# PDM-S02-V00-BatteryProtection.net
KiCad netlist of a schematic drawn in Altium Designer
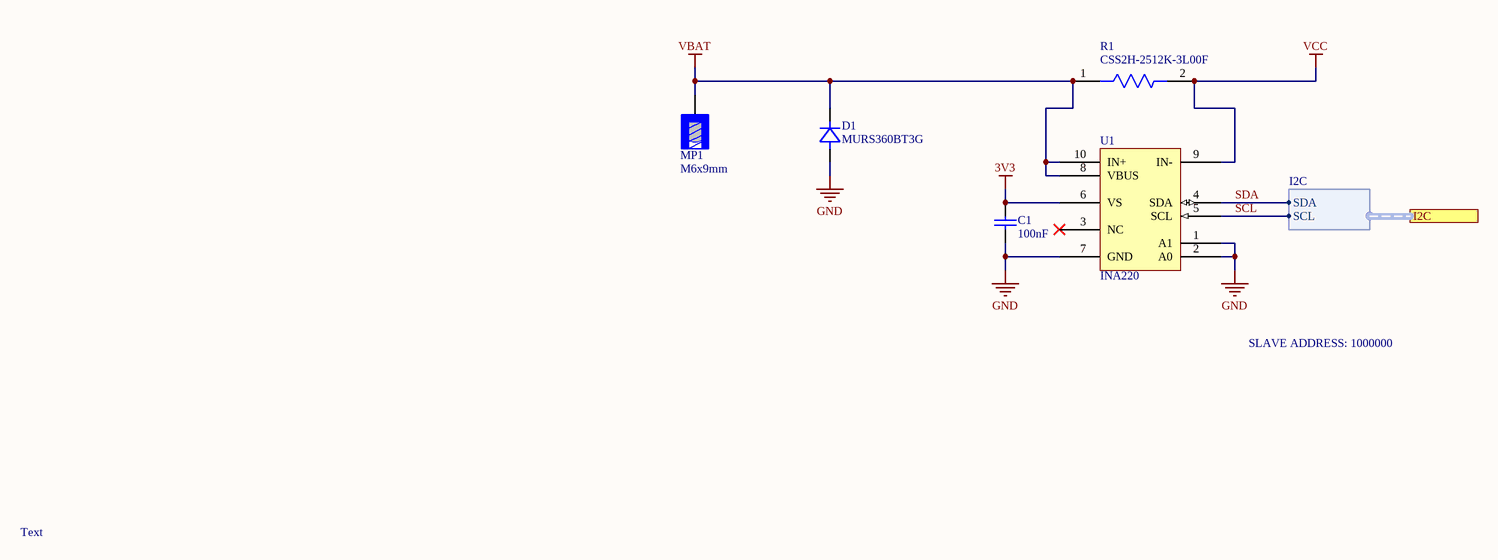
[diagram p0: PDM-S02-V00-BatteryProtection.SchDoc]

(export (version "E")
  (design (tool "Eeschema 10.0.6"))
  (components
    (comp (ref "C1")
      (value "100nF")
      (footprint "Cap_Ceramic_0603")
      (description "Capacitor, Ceramic, SMD, 100nF, 50V, 5%, X7R, 0603")
      (libsource (lib "StandardCapacitors") (part "100nF 50V 5% X7R 0603"))
    )
    (comp (ref "D1")
      (value "MURS360BT3G")
      (footprint "DO-214AA")
      (description "Diode Standard 600V 3A Surface Mount SMB")
      (libsource (lib "QUTMS_DiodeLibrary") (part "MURS360BT3G"))
    )
    (comp (ref "MP1")
      (value "M6x9mm")
      (footprint "7461084_for chemical surfaces")
      (description "WP-BUTR Press-Fit with Internal thread, two rows, 10x10mm, 8 pins, M6x9mm, 160A")
      (fields (field (name "PART NUMBER") "7461084") (field (name "PUBLISHER") "Wurth Elektronik"))
      (libsource (lib "7461084_Altium_WP-BUTR_rev19a") (part "7461084"))
    )
    (comp (ref "R1")
      (value "CSS2H-2512K-3L00F")
      (footprint "CSS2H-2512")
      (description "RES 0.003 OHM 1% 4W 2512")
      (libsource (lib "PDM-CARD-SCHLib-V00") (part "CSS2H-2512K-3L00F"))
    )
    (comp (ref "U1")
      (value "INA220")
      (footprint "VSSOP-10P")
      (libsource (lib "PDM-CARD-SCHLib-V00") (part "INA220"))
    )
  )
  (nets
    (net (code "2") (name "/SCL") (class "Default")
      (node (ref "U1") (pin "5") (pinfunction "SCL_5") (pintype "input"))
    )
    (net (code "3") (name "/SDA") (class "Default")
      (node (ref "U1") (pin "4") (pinfunction "SDA_4") (pintype "bidirectional"))
    )
    (net (code "5") (name "3V3") (class "Default")
      (node (ref "C1") (pin "2") (pinfunction "2_2") (pintype "passive"))
      (node (ref "U1") (pin "6") (pinfunction "VS_6") (pintype "passive"))
    )
    (net (code "6") (name "GND") (class "Default")
      (node (ref "C1") (pin "1") (pinfunction "1_1") (pintype "passive"))
      (node (ref "D1") (pin "A") (pinfunction "A_A") (pintype "passive"))
      (node (ref "U1") (pin "1") (pinfunction "A1_1") (pintype "passive"))
      (node (ref "U1") (pin "2") (pinfunction "A0_2") (pintype "passive"))
      (node (ref "U1") (pin "7") (pinfunction "GND_7") (pintype "passive"))
    )
    (net (code "7") (name "VBAT") (class "Default")
      (node (ref "D1") (pin "K") (pinfunction "K_K") (pintype "passive"))
      (node (ref "MP1") (pin "1") (pinfunction "1_1") (pintype "passive"))
      (node (ref "R1") (pin "1") (pinfunction "1_LOAD_1") (pintype "passive"))
      (node (ref "U1") (pin "10") (pinfunction "IN+_10") (pintype "passive"))
      (node (ref "U1") (pin "8") (pinfunction "VBUS_8") (pintype "passive"))
    )
    (net (code "8") (name "VCC") (class "Default")
      (node (ref "R1") (pin "2") (pinfunction "2_LOAD_2") (pintype "passive"))
      (node (ref "U1") (pin "9") (pinfunction "IN-_9") (pintype "passive"))
    )
    (net (code "9") (name "unconnected-(U1-NC-Pad3)") (class "Default")
      (node (ref "U1") (pin "3") (pinfunction "NC_3") (pintype "passive+no_connect"))
    )
  )
)
